# obc-v2_CM4-IRQ-CTRL.net
KiCad netlist of a schematic drawn in Altium Designer
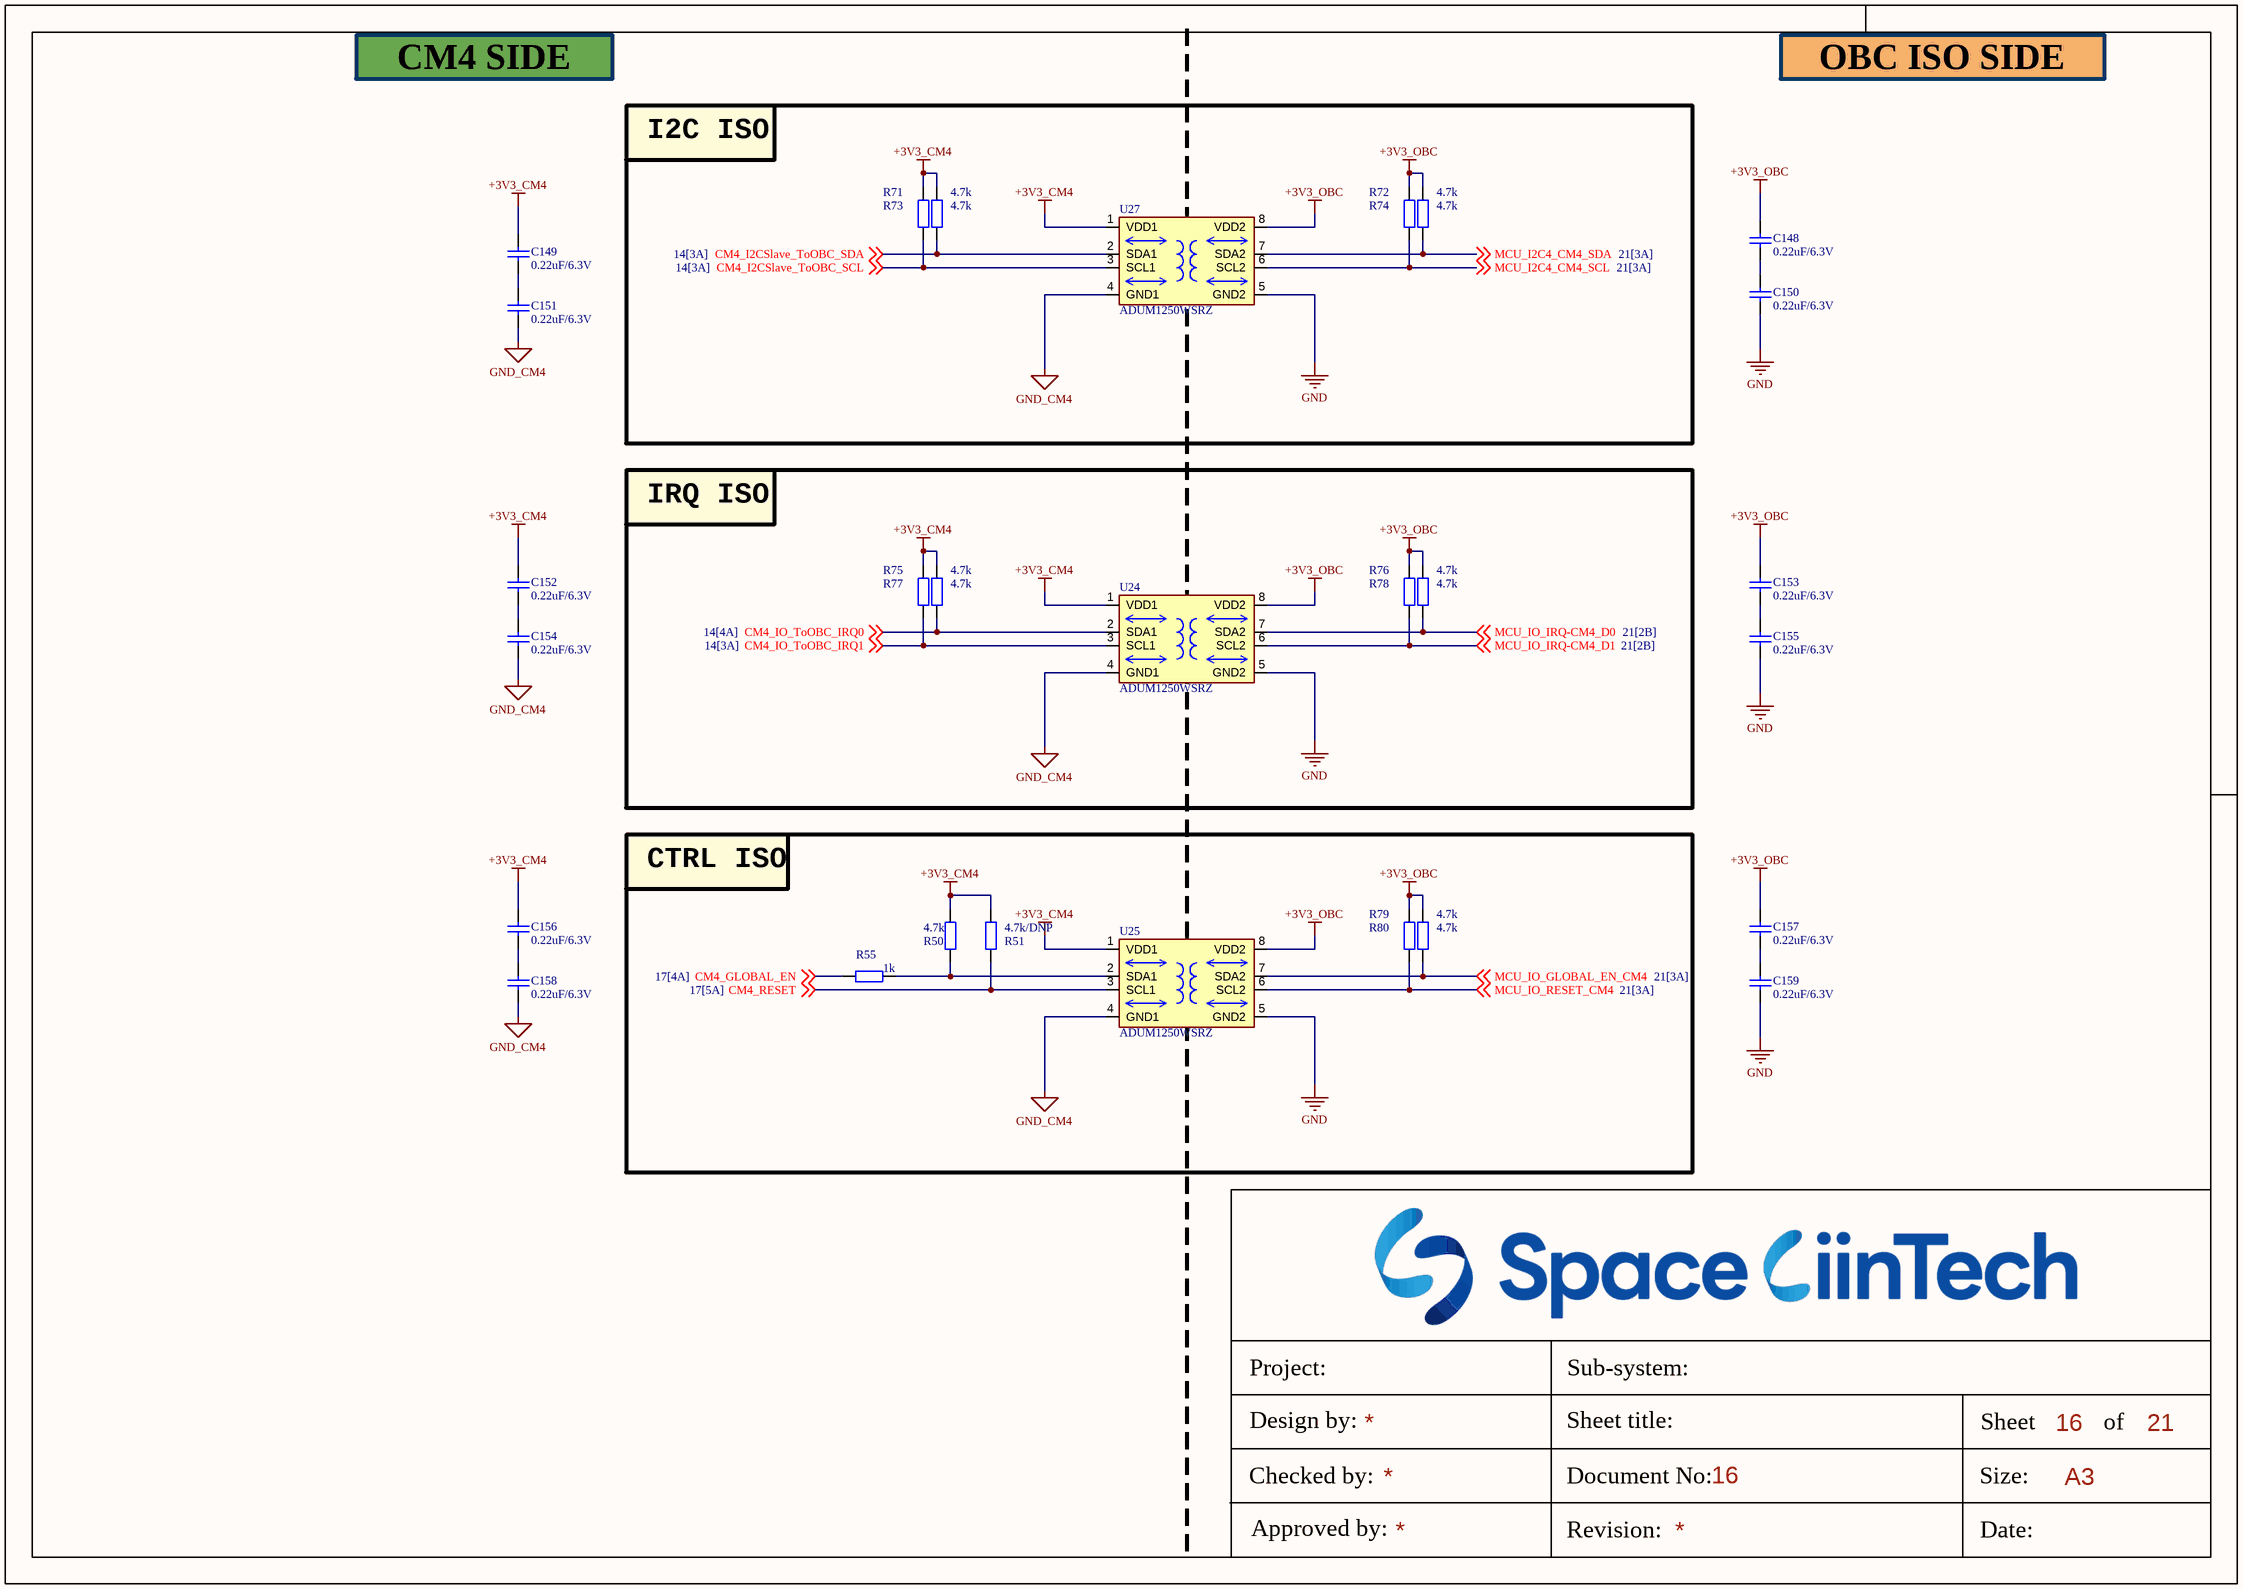
[diagram p0: obc-v2_CM4-IRQ-CTRL.SchDoc]

(export (version "E")
  (design (tool "Eeschema 10.0.6"))
  (components
    (comp (ref "C148")
      (value "0.22uF/6.3V")
      (footprint "CAP_C_1005X60")
      (description "CAPC")
      (libsource (lib "Altium_Lib_by_KhueNguyenCreator") (part "Tu 0402 33nF 10V"))
    )
    (comp (ref "C149")
      (value "0.22uF/6.3V")
      (footprint "CAP_C_1005X60")
      (description "CAPC")
      (libsource (lib "Altium_Lib_by_KhueNguyenCreator") (part "Tu 0402 33nF 10V"))
    )
    (comp (ref "C150")
      (value "0.22uF/6.3V")
      (footprint "CAP_C_1005X60")
      (description "CAPC")
      (libsource (lib "Altium_Lib_by_KhueNguyenCreator") (part "Tu 0402 33nF 10V"))
    )
    (comp (ref "C151")
      (value "0.22uF/6.3V")
      (footprint "CAP_C_1005X60")
      (description "CAPC")
      (libsource (lib "Altium_Lib_by_KhueNguyenCreator") (part "Tu 0402 33nF 10V"))
    )
    (comp (ref "C152")
      (value "0.22uF/6.3V")
      (footprint "CAP_C_1005X60")
      (description "CAPC")
      (libsource (lib "Altium_Lib_by_KhueNguyenCreator") (part "Tu 0402 33nF 10V"))
    )
    (comp (ref "C153")
      (value "0.22uF/6.3V")
      (footprint "CAP_C_1005X60")
      (description "CAPC")
      (libsource (lib "Altium_Lib_by_KhueNguyenCreator") (part "Tu 0402 33nF 10V"))
    )
    (comp (ref "C154")
      (value "0.22uF/6.3V")
      (footprint "CAP_C_1005X60")
      (description "CAPC")
      (libsource (lib "Altium_Lib_by_KhueNguyenCreator") (part "Tu 0402 33nF 10V"))
    )
    (comp (ref "C155")
      (value "0.22uF/6.3V")
      (footprint "CAP_C_1005X60")
      (description "CAPC")
      (libsource (lib "Altium_Lib_by_KhueNguyenCreator") (part "Tu 0402 33nF 10V"))
    )
    (comp (ref "C156")
      (value "0.22uF/6.3V")
      (footprint "CAP_C_1005X60")
      (description "CAPC")
      (libsource (lib "Altium_Lib_by_KhueNguyenCreator") (part "Tu 0402 33nF 10V"))
    )
    (comp (ref "C157")
      (value "0.22uF/6.3V")
      (footprint "CAP_C_1005X60")
      (description "CAPC")
      (libsource (lib "Altium_Lib_by_KhueNguyenCreator") (part "Tu 0402 33nF 10V"))
    )
    (comp (ref "C158")
      (value "0.22uF/6.3V")
      (footprint "CAP_C_1005X60")
      (description "CAPC")
      (libsource (lib "Altium_Lib_by_KhueNguyenCreator") (part "Tu 0402 33nF 10V"))
    )
    (comp (ref "C159")
      (value "0.22uF/6.3V")
      (footprint "CAP_C_1005X60")
      (description "CAPC")
      (libsource (lib "Altium_Lib_by_KhueNguyenCreator") (part "Tu 0402 33nF 10V"))
    )
    (comp (ref "R50")
      (value "4.7k")
      (footprint "RES_C_1608X60")
      (description "RES")
      (libsource (lib "Altium_Lib_by_KhueNguyenCreator") (part "Tro 0603 1% 10k"))
    )
    (comp (ref "R51")
      (value "4.7k/DNP")
      (footprint "RES_C_1608X60")
      (description "RES")
      (libsource (lib "Altium_Lib_by_KhueNguyenCreator") (part "Tro 0603 1% 10k"))
    )
    (comp (ref "R55")
      (value "1k")
      (footprint "RES_C_1608X60")
      (description "RES")
      (libsource (lib "Altium_Lib_by_KhueNguyenCreator") (part "Tro 0603 1% 10k"))
    )
    (comp (ref "R71")
      (value "4.7k")
      (footprint "RES_C_1608X60")
      (description "RES")
      (libsource (lib "Altium_Lib_by_KhueNguyenCreator") (part "Tro 0603 1% 10k"))
    )
    (comp (ref "R72")
      (value "4.7k")
      (footprint "RES_C_1608X60")
      (description "RES")
      (libsource (lib "Altium_Lib_by_KhueNguyenCreator") (part "Tro 0603 1% 10k"))
    )
    (comp (ref "R73")
      (value "4.7k")
      (footprint "RES_C_1608X60")
      (description "RES")
      (libsource (lib "Altium_Lib_by_KhueNguyenCreator") (part "Tro 0603 1% 10k"))
    )
    (comp (ref "R74")
      (value "4.7k")
      (footprint "RES_C_1608X60")
      (description "RES")
      (libsource (lib "Altium_Lib_by_KhueNguyenCreator") (part "Tro 0603 1% 10k"))
    )
    (comp (ref "R75")
      (value "4.7k")
      (footprint "RES_C_1608X60")
      (description "RES")
      (libsource (lib "Altium_Lib_by_KhueNguyenCreator") (part "Tro 0603 1% 10k"))
    )
    (comp (ref "R76")
      (value "4.7k")
      (footprint "RES_C_1608X60")
      (description "RES")
      (libsource (lib "Altium_Lib_by_KhueNguyenCreator") (part "Tro 0603 1% 10k"))
    )
    (comp (ref "R77")
      (value "4.7k")
      (footprint "RES_C_1608X60")
      (description "RES")
      (libsource (lib "Altium_Lib_by_KhueNguyenCreator") (part "Tro 0603 1% 10k"))
    )
    (comp (ref "R78")
      (value "4.7k")
      (footprint "RES_C_1608X60")
      (description "RES")
      (libsource (lib "Altium_Lib_by_KhueNguyenCreator") (part "Tro 0603 1% 10k"))
    )
    (comp (ref "R79")
      (value "4.7k")
      (footprint "RES_C_1608X60")
      (description "RES")
      (libsource (lib "Altium_Lib_by_KhueNguyenCreator") (part "Tro 0603 1% 10k"))
    )
    (comp (ref "R80")
      (value "4.7k")
      (footprint "RES_C_1608X60")
      (description "RES")
      (libsource (lib "Altium_Lib_by_KhueNguyenCreator") (part "Tro 0603 1% 10k"))
    )
    (comp (ref "U24")
      (value "ADUM1250WSRZ")
      (footprint "SOIC127P602X173-8N")
      (description "I虏C Digital Isolator 2500Vrms 2 Channel 1Mbps 25kV/碌s CMTI 8-SOIC (0.154\", 3.90mm Width)")
      (fields (field (name "MF") "Analog Devices") (field (name "MP") "ADUM1250"))
      (libsource (lib "ADUM1250") (part "ADUM1250"))
    )
    (comp (ref "U25")
      (value "ADUM1250WSRZ")
      (footprint "SOIC127P602X173-8N")
      (description "I虏C Digital Isolator 2500Vrms 2 Channel 1Mbps 25kV/碌s CMTI 8-SOIC (0.154\", 3.90mm Width)")
      (fields (field (name "MF") "Analog Devices") (field (name "MP") "ADUM1250"))
      (libsource (lib "ADUM1250") (part "ADUM1250"))
    )
    (comp (ref "U27")
      (value "ADUM1250WSRZ")
      (footprint "SOIC127P602X173-8N")
      (description "I虏C Digital Isolator 2500Vrms 2 Channel 1Mbps 25kV/碌s CMTI 8-SOIC (0.154\", 3.90mm Width)")
      (fields (field (name "MF") "Analog Devices") (field (name "MP") "ADUM1250"))
      (libsource (lib "ADUM1250") (part "ADUM1250"))
    )
  )
  (nets
    (net (code "1") (name "+3V3_CM4") (class "Default")
      (node (ref "C149") (pin "1") (pinfunction "1_1") (pintype "passive"))
      (node (ref "C152") (pin "1") (pinfunction "1_1") (pintype "passive"))
      (node (ref "C156") (pin "1") (pinfunction "1_1") (pintype "passive"))
      (node (ref "R50") (pin "2") (pinfunction "2_2") (pintype "passive"))
      (node (ref "R51") (pin "2") (pinfunction "2_2") (pintype "passive"))
      (node (ref "R71") (pin "2") (pinfunction "2_2") (pintype "passive"))
      (node (ref "R73") (pin "2") (pinfunction "2_2") (pintype "passive"))
      (node (ref "R75") (pin "2") (pinfunction "2_2") (pintype "passive"))
      (node (ref "R77") (pin "2") (pinfunction "2_2") (pintype "passive"))
      (node (ref "U24") (pin "1") (pinfunction "VDD1_1") (pintype "power_in"))
      (node (ref "U25") (pin "1") (pinfunction "VDD1_1") (pintype "power_in"))
      (node (ref "U27") (pin "1") (pinfunction "VDD1_1") (pintype "power_in"))
    )
    (net (code "2") (name "+3V3_OBC") (class "Default")
      (node (ref "C148") (pin "1") (pinfunction "1_1") (pintype "passive"))
      (node (ref "C153") (pin "1") (pinfunction "1_1") (pintype "passive"))
      (node (ref "C157") (pin "1") (pinfunction "1_1") (pintype "passive"))
      (node (ref "R72") (pin "2") (pinfunction "2_2") (pintype "passive"))
      (node (ref "R74") (pin "2") (pinfunction "2_2") (pintype "passive"))
      (node (ref "R76") (pin "2") (pinfunction "2_2") (pintype "passive"))
      (node (ref "R78") (pin "2") (pinfunction "2_2") (pintype "passive"))
      (node (ref "R79") (pin "2") (pinfunction "2_2") (pintype "passive"))
      (node (ref "R80") (pin "2") (pinfunction "2_2") (pintype "passive"))
      (node (ref "U24") (pin "8") (pinfunction "VDD2_8") (pintype "power_in"))
      (node (ref "U25") (pin "8") (pinfunction "VDD2_8") (pintype "power_in"))
      (node (ref "U27") (pin "8") (pinfunction "VDD2_8") (pintype "power_in"))
    )
    (net (code "3") (name "CM4_GLOBAL_EN") (class "Default")
      (node (ref "R55") (pin "2") (pinfunction "2_2") (pintype "passive"))
    )
    (net (code "4") (name "CM4_I2CSlave_ToOBC_SCL") (class "Default")
      (node (ref "R71") (pin "1") (pinfunction "1_1") (pintype "passive"))
      (node (ref "U27") (pin "3") (pinfunction "SCL1_3") (pintype "bidirectional"))
    )
    (net (code "5") (name "CM4_I2CSlave_ToOBC_SDA") (class "Default")
      (node (ref "R73") (pin "1") (pinfunction "1_1") (pintype "passive"))
      (node (ref "U27") (pin "2") (pinfunction "SDA1_2") (pintype "bidirectional"))
    )
    (net (code "6") (name "CM4_IO_ToOBC_IRQ0") (class "Default")
      (node (ref "R77") (pin "1") (pinfunction "1_1") (pintype "passive"))
      (node (ref "U24") (pin "2") (pinfunction "SDA1_2") (pintype "bidirectional"))
    )
    (net (code "7") (name "CM4_IO_ToOBC_IRQ1") (class "Default")
      (node (ref "R75") (pin "1") (pinfunction "1_1") (pintype "passive"))
      (node (ref "U24") (pin "3") (pinfunction "SCL1_3") (pintype "bidirectional"))
    )
    (net (code "8") (name "CM4_RESET") (class "Default")
      (node (ref "R51") (pin "1") (pinfunction "1_1") (pintype "passive"))
      (node (ref "U25") (pin "3") (pinfunction "SCL1_3") (pintype "bidirectional"))
    )
    (net (code "9") (name "GND") (class "Default")
      (node (ref "C150") (pin "2") (pinfunction "2_2") (pintype "passive"))
      (node (ref "C155") (pin "2") (pinfunction "2_2") (pintype "passive"))
      (node (ref "C159") (pin "2") (pinfunction "2_2") (pintype "passive"))
      (node (ref "U24") (pin "5") (pinfunction "GND2_5") (pintype "power_in"))
      (node (ref "U25") (pin "5") (pinfunction "GND2_5") (pintype "power_in"))
      (node (ref "U27") (pin "5") (pinfunction "GND2_5") (pintype "power_in"))
    )
    (net (code "10") (name "GND_CM4") (class "Default")
      (node (ref "C151") (pin "2") (pinfunction "2_2") (pintype "passive"))
      (node (ref "C154") (pin "2") (pinfunction "2_2") (pintype "passive"))
      (node (ref "C158") (pin "2") (pinfunction "2_2") (pintype "passive"))
      (node (ref "U24") (pin "4") (pinfunction "GND1_4") (pintype "power_in"))
      (node (ref "U25") (pin "4") (pinfunction "GND1_4") (pintype "power_in"))
      (node (ref "U27") (pin "4") (pinfunction "GND1_4") (pintype "power_in"))
    )
    (net (code "11") (name "MCU_I2C4_CM4_SCL") (class "Default")
      (node (ref "R72") (pin "1") (pinfunction "1_1") (pintype "passive"))
      (node (ref "U27") (pin "6") (pinfunction "SCL2_6") (pintype "bidirectional"))
    )
    (net (code "12") (name "MCU_I2C4_CM4_SDA") (class "Default")
      (node (ref "R74") (pin "1") (pinfunction "1_1") (pintype "passive"))
      (node (ref "U27") (pin "7") (pinfunction "SDA2_7") (pintype "bidirectional"))
    )
    (net (code "13") (name "MCU_IO_GLOBAL_EN_CM4") (class "Default")
      (node (ref "R80") (pin "1") (pinfunction "1_1") (pintype "passive"))
      (node (ref "U25") (pin "7") (pinfunction "SDA2_7") (pintype "bidirectional"))
    )
    (net (code "14") (name "MCU_IO_IRQ-CM4_D0") (class "Default")
      (node (ref "R78") (pin "1") (pinfunction "1_1") (pintype "passive"))
      (node (ref "U24") (pin "7") (pinfunction "SDA2_7") (pintype "bidirectional"))
    )
    (net (code "15") (name "MCU_IO_IRQ-CM4_D1") (class "Default")
      (node (ref "R76") (pin "1") (pinfunction "1_1") (pintype "passive"))
      (node (ref "U24") (pin "6") (pinfunction "SCL2_6") (pintype "bidirectional"))
    )
    (net (code "16") (name "MCU_IO_RESET_CM4") (class "Default")
      (node (ref "R79") (pin "1") (pinfunction "1_1") (pintype "passive"))
      (node (ref "U25") (pin "6") (pinfunction "SCL2_6") (pintype "bidirectional"))
    )
    (net (code "17") (name "Net-(C148-Pad2)") (class "Default")
      (node (ref "C148") (pin "2") (pinfunction "2_2") (pintype "passive"))
      (node (ref "C150") (pin "1") (pinfunction "1_1") (pintype "passive"))
    )
    (net (code "18") (name "Net-(C149-Pad2)") (class "Default")
      (node (ref "C149") (pin "2") (pinfunction "2_2") (pintype "passive"))
      (node (ref "C151") (pin "1") (pinfunction "1_1") (pintype "passive"))
    )
    (net (code "19") (name "Net-(C152-Pad2)") (class "Default")
      (node (ref "C152") (pin "2") (pinfunction "2_2") (pintype "passive"))
      (node (ref "C154") (pin "1") (pinfunction "1_1") (pintype "passive"))
    )
    (net (code "20") (name "Net-(C153-Pad2)") (class "Default")
      (node (ref "C153") (pin "2") (pinfunction "2_2") (pintype "passive"))
      (node (ref "C155") (pin "1") (pinfunction "1_1") (pintype "passive"))
    )
    (net (code "21") (name "Net-(C156-Pad2)") (class "Default")
      (node (ref "C156") (pin "2") (pinfunction "2_2") (pintype "passive"))
      (node (ref "C158") (pin "1") (pinfunction "1_1") (pintype "passive"))
    )
    (net (code "22") (name "Net-(C157-Pad2)") (class "Default")
      (node (ref "C157") (pin "2") (pinfunction "2_2") (pintype "passive"))
      (node (ref "C159") (pin "1") (pinfunction "1_1") (pintype "passive"))
    )
    (net (code "23") (name "Net-(U25-SDA1)") (class "Default")
      (node (ref "R50") (pin "1") (pinfunction "1_1") (pintype "passive"))
      (node (ref "R55") (pin "1") (pinfunction "1_1") (pintype "passive"))
      (node (ref "U25") (pin "2") (pinfunction "SDA1_2") (pintype "bidirectional"))
    )
  )
)
